# schematic.net
KiCad netlist of a schematic drawn in Altium Designer
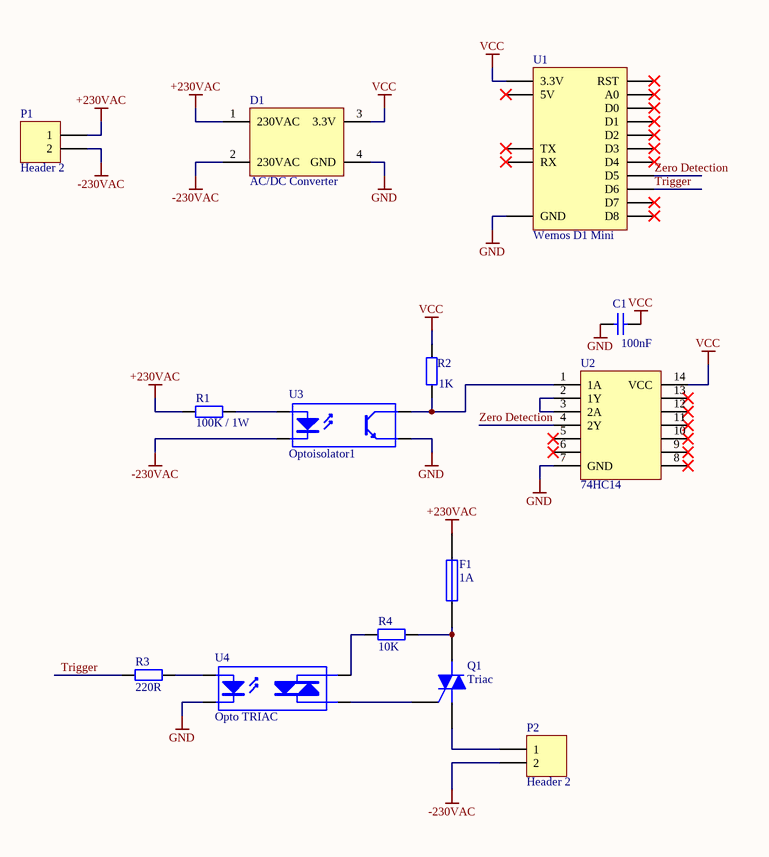
[diagram p0: schematic.SchDoc]

(export (version "E")
  (design (tool "Eeschema 10.0.6"))
  (components
    (comp (ref "C1")
      (value "100nF")
      (footprint "RAD-0.3")
      (description "Capacitor")
      (fields (field (name "Comment") "Cap") (field (name "PUBLISHER") "Altium Limited"))
      (libsource (lib "Miscellaneous Devices") (part "Cap"))
    )
    (comp (ref "D1")
      (value "AC/DC Converter")
      (footprint "D-46_6A")
      (fields (field (name "PUBLISHER") "Altium Limited"))
      (libsource (lib "RemoteDimmer") (part "AC/DC Converter"))
    )
    (comp (ref "F1")
      (value "1A")
      (footprint "PIN-W2/E2.8")
      (description "Fuse")
      (fields (field (name "PUBLISHER") "Altium Limited"))
      (libsource (lib "Miscellaneous Devices") (part "Fuse 1"))
    )
    (comp (ref "P1")
      (value "Header 2")
      (footprint "HDR1X2")
      (description "Header, 2-Pin")
      (fields (field (name "PUBLISHER") "Altium Limited"))
      (libsource (lib "Miscellaneous Connectors") (part "Header 2"))
    )
    (comp (ref "P2")
      (value "Header 2")
      (footprint "HDR1X2")
      (description "Header, 2-Pin")
      (fields (field (name "PUBLISHER") "Altium Limited"))
      (libsource (lib "SchematicLibrary") (part "Header 2"))
    )
    (comp (ref "Q1")
      (value "Triac")
      (footprint "369-03")
      (description "Silicon Bidirectional Triode Thyristor")
      (fields (field (name "PUBLISHER") "Altium Limited"))
      (libsource (lib "Miscellaneous Devices") (part "Triac"))
    )
    (comp (ref "R1")
      (value "100K / 1W")
      (footprint "AXIAL-0.4")
      (description "Resistor")
      (fields (field (name "Comment") "Res2") (field (name "PUBLISHER") "Altium Limited"))
      (libsource (lib "SchematicLibrary") (part "Res2"))
    )
    (comp (ref "R2")
      (value "1K")
      (footprint "AXIAL-0.4")
      (description "Resistor")
      (fields (field (name "Comment") "Res2") (field (name "PUBLISHER") "Altium Limited"))
      (libsource (lib "") (part "Res2_1"))
    )
    (comp (ref "R3")
      (value "220R")
      (footprint "AXIAL-0.4")
      (description "Resistor")
      (fields (field (name "Comment") "Res2") (field (name "PUBLISHER") "Altium Limited"))
      (libsource (lib "SchematicLibrary") (part "Res2"))
    )
    (comp (ref "R4")
      (value "10K")
      (footprint "AXIAL-0.4")
      (description "Resistor")
      (fields (field (name "Comment") "Res2") (field (name "PUBLISHER") "Altium Limited"))
      (libsource (lib "SchematicLibrary") (part "Res2"))
    )
    (comp (ref "U1") (value "Wemos D1 Mini") (libsource (lib "SchematicLibrary") (part "WemosD1Mini")))
    (comp (ref "U2")
      (value "74HC14")
      (footprint "SOT403-1_L")
      (description "Generic 8-Bit A/D Converter")
      (fields (field (name "PUBLISHER") "Altium Limited"))
      (libsource (lib "SchematicLibrary") (part "Schmitt-Trigger 74HC14"))
    )
    (comp (ref "U3")
      (value "Optoisolator1")
      (footprint "DIP-4")
      (description "4-Pin Phototransistor Optocoupler")
      (fields (field (name "PUBLISHER") "Altium Limited"))
      (libsource (lib "Miscellaneous Devices") (part "Optoisolator1"))
    )
    (comp (ref "U4")
      (value "Opto TRIAC")
      (footprint "NPSIP4A")
      (description "Opto-Triac")
      (fields (field (name "PUBLISHER") "Altium Limited"))
      (libsource (lib "Miscellaneous Devices") (part "Opto TRIAC"))
    )
  )
  (nets
    (net (code "1") (name "+230VAC") (class "Default")
      (node (ref "D1") (pin "1") (pinfunction "230VAC_1") (pintype "passive"))
      (node (ref "F1") (pin "2") (pinfunction "2_2") (pintype "passive"))
      (node (ref "P1") (pin "1") (pinfunction "1_1") (pintype "passive"))
      (node (ref "R1") (pin "1") (pinfunction "1_1") (pintype "passive"))
    )
    (net (code "2") (name "-230VAC") (class "Default")
      (node (ref "D1") (pin "2") (pinfunction "230VAC_2") (pintype "passive"))
      (node (ref "P1") (pin "2") (pinfunction "2_2") (pintype "passive"))
      (node (ref "P2") (pin "2") (pinfunction "2_2") (pintype "passive"))
      (node (ref "U3") (pin "2") (pinfunction "K_2") (pintype "passive"))
    )
    (net (code "3") (name "/Trigger") (class "Default")
      (node (ref "R3") (pin "1") (pinfunction "1_1") (pintype "passive"))
      (node (ref "U1") (pin "12") (pinfunction "D6_12") (pintype "passive"))
    )
    (net (code "4") (name "/Zero Detection") (class "Default")
      (node (ref "U1") (pin "13") (pinfunction "D5_13") (pintype "passive"))
      (node (ref "U2") (pin "4") (pinfunction "2Y_4") (pintype "passive"))
    )
    (net (code "5") (name "GND") (class "Default")
      (node (ref "C1") (pin "1") (pinfunction "1_1") (pintype "passive"))
      (node (ref "D1") (pin "4") (pinfunction "GND_4") (pintype "passive"))
      (node (ref "U1") (pin "7") (pinfunction "GND_7") (pintype "passive"))
      (node (ref "U2") (pin "7") (pinfunction "GND_7") (pintype "passive"))
      (node (ref "U3") (pin "3") (pinfunction "E_3") (pintype "passive"))
      (node (ref "U4") (pin "2") (pinfunction "K_2") (pintype "passive"))
    )
    (net (code "6") (name "Net-(Q1-G)") (class "Default")
      (node (ref "Q1") (pin "3") (pinfunction "G_3") (pintype "passive"))
      (node (ref "U4") (pin "4") (pinfunction "A/K_4") (pintype "passive"))
    )
    (net (code "7") (name "Net-(Q1-M1)") (class "Default")
      (node (ref "P2") (pin "1") (pinfunction "1_1") (pintype "passive"))
      (node (ref "Q1") (pin "1") (pinfunction "M1_1") (pintype "passive"))
    )
    (net (code "8") (name "Net-(Q1-M2)") (class "Default")
      (node (ref "F1") (pin "1") (pinfunction "1_1") (pintype "passive"))
      (node (ref "Q1") (pin "2") (pinfunction "M2_2") (pintype "passive"))
      (node (ref "R4") (pin "2") (pinfunction "2_2") (pintype "passive"))
    )
    (net (code "9") (name "Net-(R4-Pad1)") (class "Default")
      (node (ref "R4") (pin "1") (pinfunction "1_1") (pintype "passive"))
      (node (ref "U4") (pin "3") (pinfunction "A/K_3") (pintype "passive"))
    )
    (net (code "10") (name "Net-(U2-1A)") (class "Default")
      (node (ref "R2") (pin "1") (pinfunction "1_1") (pintype "passive"))
      (node (ref "U2") (pin "1") (pinfunction "1A_1") (pintype "passive"))
      (node (ref "U3") (pin "4") (pinfunction "C_4") (pintype "passive"))
    )
    (net (code "11") (name "Net-(U2-1Y)") (class "Default")
      (node (ref "U2") (pin "2") (pinfunction "1Y_2") (pintype "passive"))
      (node (ref "U2") (pin "3") (pinfunction "2A_3") (pintype "passive"))
    )
    (net (code "12") (name "Net-(U3-A)") (class "Default")
      (node (ref "R1") (pin "2") (pinfunction "2_2") (pintype "passive"))
      (node (ref "U3") (pin "1") (pinfunction "A_1") (pintype "passive"))
    )
    (net (code "13") (name "Net-(U4-A)") (class "Default")
      (node (ref "R3") (pin "2") (pinfunction "2_2") (pintype "passive"))
      (node (ref "U4") (pin "1") (pinfunction "A_1") (pintype "passive"))
    )
    (net (code "14") (name "VCC") (class "Default")
      (node (ref "C1") (pin "2") (pinfunction "2_2") (pintype "passive"))
      (node (ref "D1") (pin "3") (pinfunction "3.3V_3") (pintype "passive"))
      (node (ref "R2") (pin "2") (pinfunction "2_2") (pintype "passive"))
      (node (ref "U1") (pin "9") (pinfunction "3.3V_9") (pintype "passive"))
      (node (ref "U2") (pin "14") (pinfunction "VCC_14") (pintype "power_in"))
    )
    (net (code "15") (name "unconnected-(U1-5V-Pad8)") (class "Default")
      (node (ref "U1") (pin "8") (pinfunction "5V_8") (pintype "passive+no_connect"))
    )
    (net (code "16") (name "unconnected-(U1-A0-Pad15)") (class "Default")
      (node (ref "U1") (pin "15") (pinfunction "A0_15") (pintype "passive+no_connect"))
    )
    (net (code "17") (name "unconnected-(U1-D0-Pad14)") (class "Default")
      (node (ref "U1") (pin "14") (pinfunction "D0_14") (pintype "passive+no_connect"))
    )
    (net (code "18") (name "unconnected-(U1-D1-Pad3)") (class "Default")
      (node (ref "U1") (pin "3") (pinfunction "D1_3") (pintype "passive+no_connect"))
    )
    (net (code "19") (name "unconnected-(U1-D2-Pad4)") (class "Default")
      (node (ref "U1") (pin "4") (pinfunction "D2_4") (pintype "passive+no_connect"))
    )
    (net (code "20") (name "unconnected-(U1-D3-Pad5)") (class "Default")
      (node (ref "U1") (pin "5") (pinfunction "D3_5") (pintype "passive+no_connect"))
    )
    (net (code "21") (name "unconnected-(U1-D4-Pad6)") (class "Default")
      (node (ref "U1") (pin "6") (pinfunction "D4_6") (pintype "passive+no_connect"))
    )
    (net (code "22") (name "unconnected-(U1-D7-Pad11)") (class "Default")
      (node (ref "U1") (pin "11") (pinfunction "D7_11") (pintype "passive+no_connect"))
    )
    (net (code "23") (name "unconnected-(U1-D8-Pad10)") (class "Default")
      (node (ref "U1") (pin "10") (pinfunction "D8_10") (pintype "passive+no_connect"))
    )
    (net (code "24") (name "unconnected-(U1-RST-Pad16)") (class "Default")
      (node (ref "U1") (pin "16") (pinfunction "RST_16") (pintype "passive+no_connect"))
    )
    (net (code "25") (name "unconnected-(U1-RX-Pad2)") (class "Default")
      (node (ref "U1") (pin "2") (pinfunction "RX_2") (pintype "passive+no_connect"))
    )
    (net (code "26") (name "unconnected-(U1-TX-Pad1)") (class "Default")
      (node (ref "U1") (pin "1") (pinfunction "TX_1") (pintype "passive+no_connect"))
    )
    (net (code "27") (name "unconnected-(U2-Pad5)") (class "Default")
      (node (ref "U2") (pin "5") (pintype "passive+no_connect"))
    )
    (net (code "28") (name "unconnected-(U2-Pad6)") (class "Default")
      (node (ref "U2") (pin "6") (pintype "passive+no_connect"))
    )
    (net (code "29") (name "unconnected-(U2-Pad8)") (class "Default")
      (node (ref "U2") (pin "8") (pintype "power_in+no_connect"))
    )
    (net (code "30") (name "unconnected-(U2-Pad9)") (class "Default")
      (node (ref "U2") (pin "9") (pintype "power_in+no_connect"))
    )
    (net (code "31") (name "unconnected-(U2-Pad10)") (class "Default")
      (node (ref "U2") (pin "10") (pintype "power_in+no_connect"))
    )
    (net (code "32") (name "unconnected-(U2-Pad11)") (class "Default")
      (node (ref "U2") (pin "11") (pintype "power_in+no_connect"))
    )
    (net (code "33") (name "unconnected-(U2-Pad12)") (class "Default")
      (node (ref "U2") (pin "12") (pintype "power_in+no_connect"))
    )
    (net (code "34") (name "unconnected-(U2-Pad13)") (class "Default")
      (node (ref "U2") (pin "13") (pintype "power_in+no_connect"))
    )
  )
)
